# ground-station.net
KiCad netlist of a schematic drawn in Altium Designer
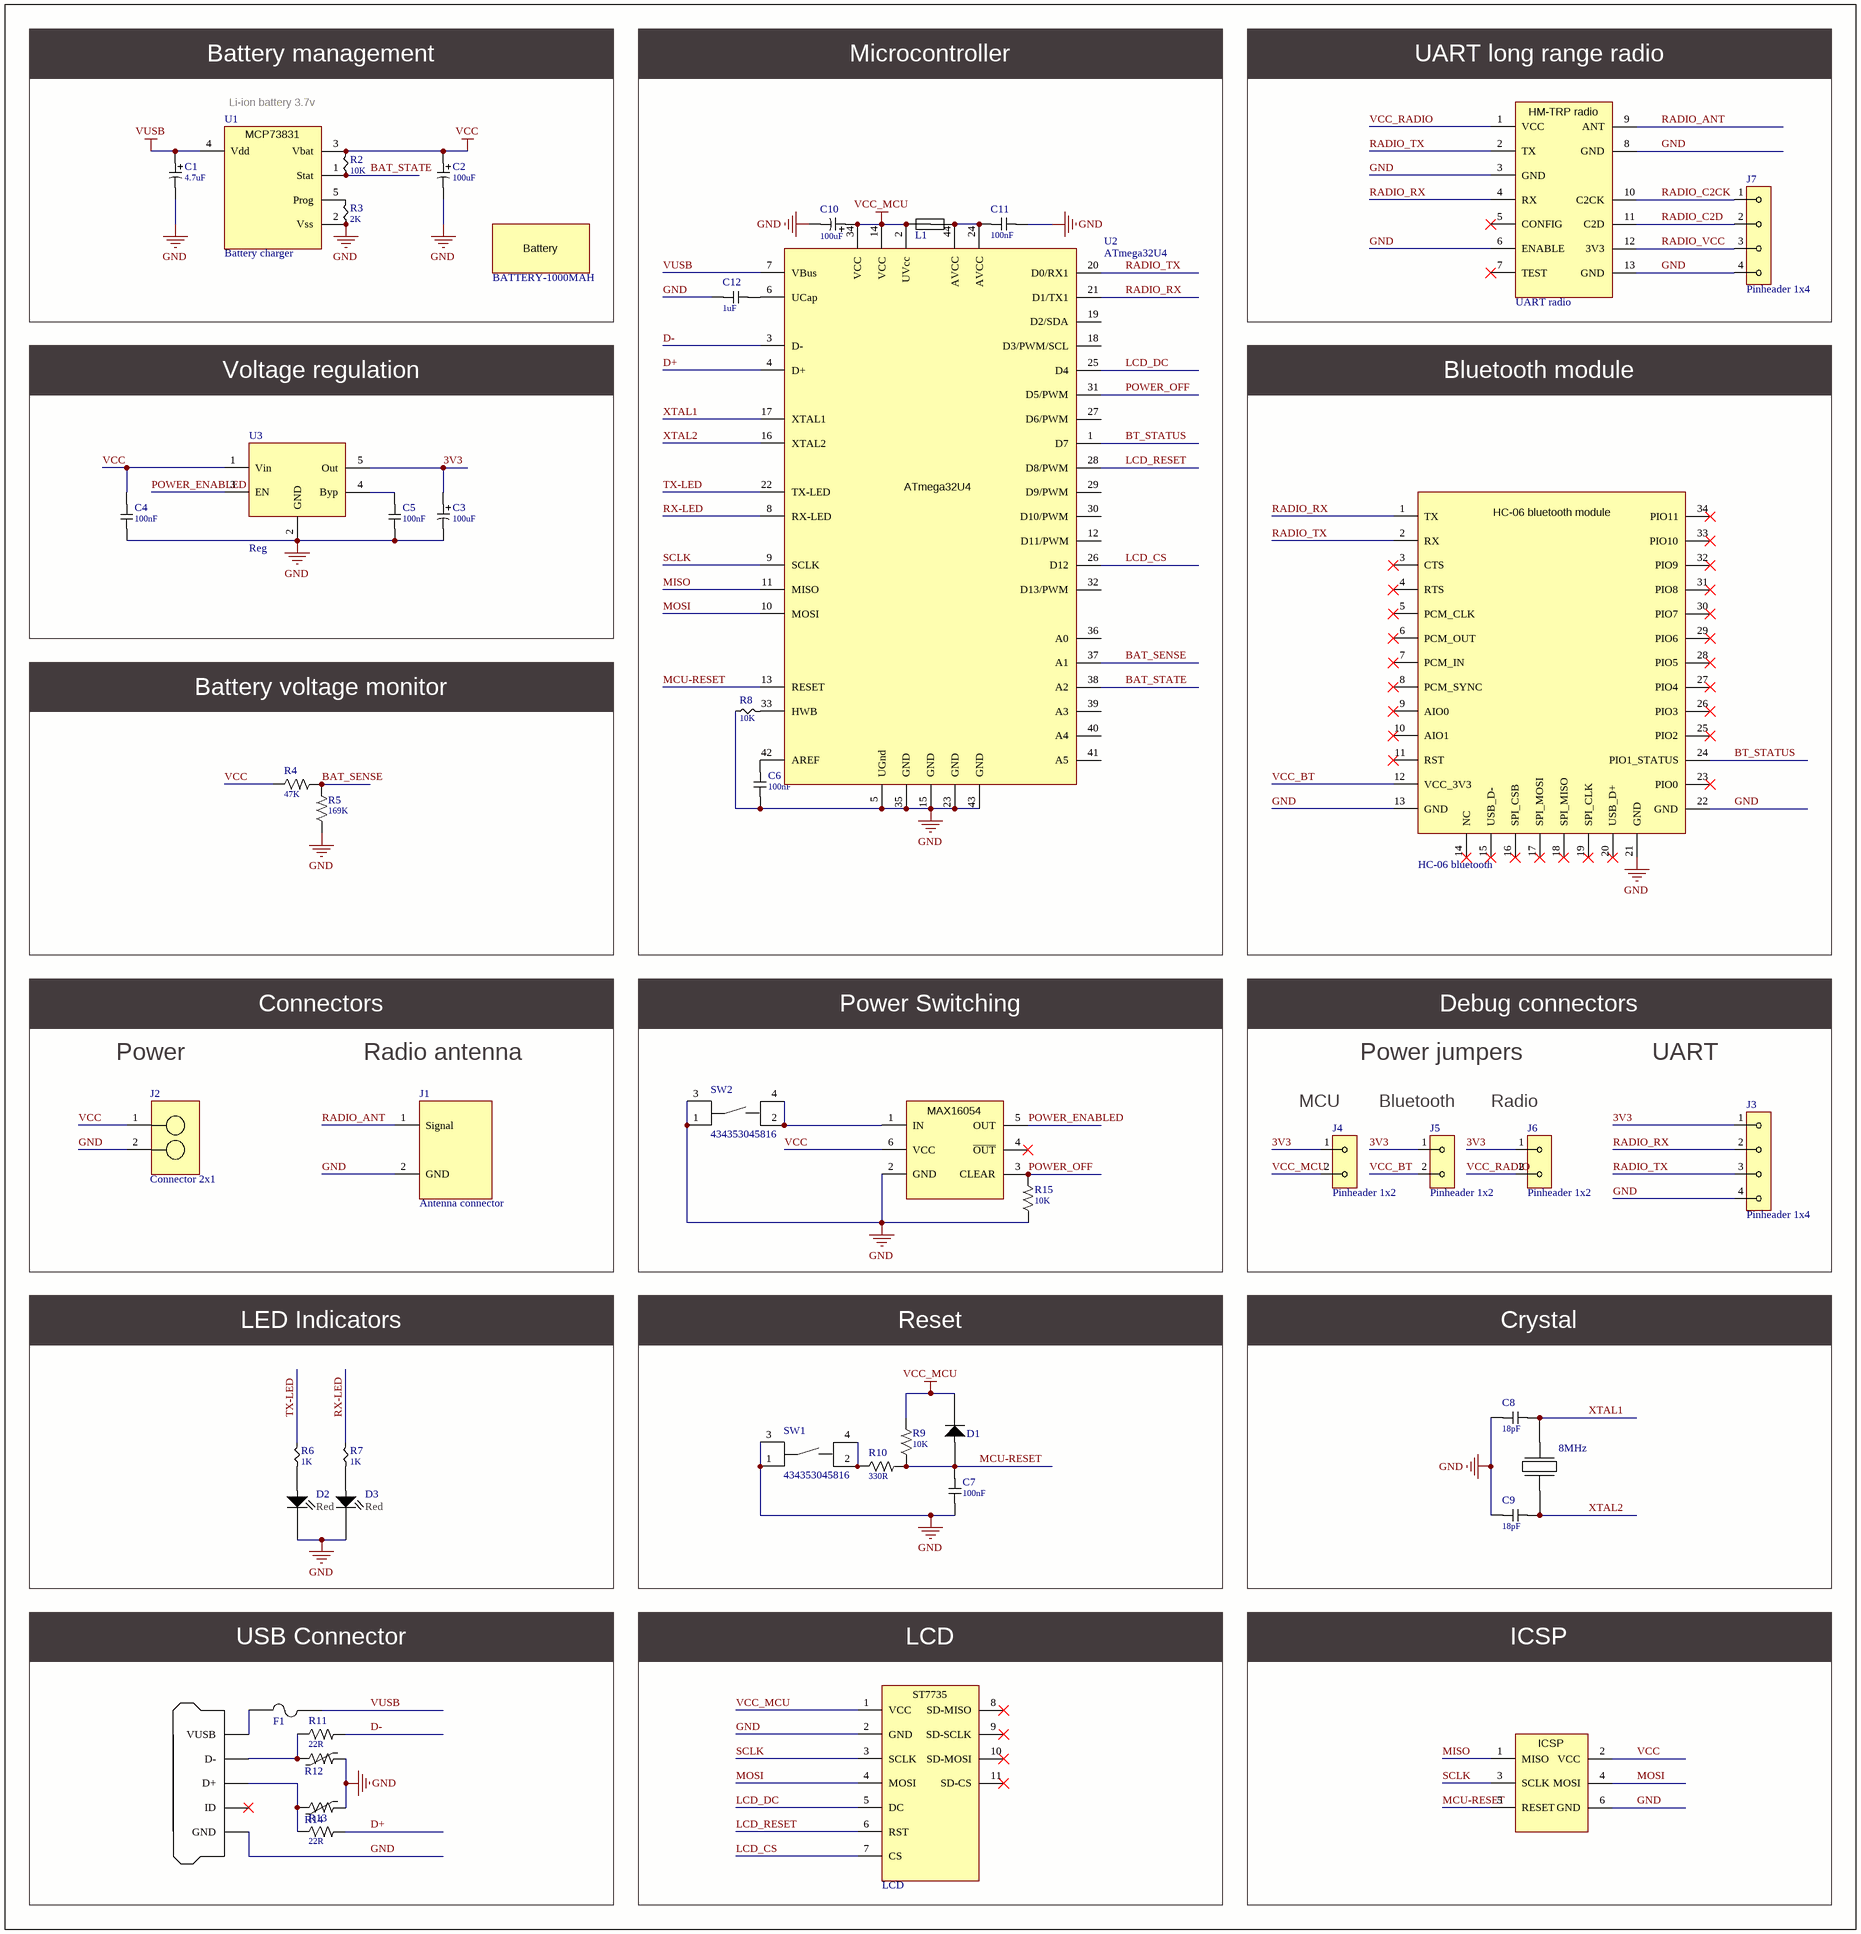
[diagram p0: ground-station.SchDoc]

(export (version "E")
  (design (tool "Eeschema 10.0.6"))
  (components
    (comp (ref "B1")
      (value "BATTERY-1000MAH")
      (footprint "BATTERY-1000MAH")
      (description "Battery")
      (libsource (lib "custom") (part "BATTERY-1000MAH"))
    )
    (comp (ref "BT1")
      (value "HC-06 bluetooth")
      (footprint "HC-06-BLUETOOTH")
      (description "HC-06 bluetooth module")
      (libsource (lib "custom") (part "HC-06-BLUETOOTH"))
    )
    (comp (ref "C1")
      (value "4.7uF")
      (footprint "CAP-0603-POL")
      (description "Polarized capacitor")
      (fields (field (name "Comment") "CAPACITOR-POLARIZED"))
      (libsource (lib "custom") (part "CAPACITOR-POLARIZED"))
    )
    (comp (ref "C2")
      (value "100uF")
      (footprint "CAP-1206-POL")
      (description "Polarized capacitor")
      (fields (field (name "Comment") "CAPACITOR-POLARIZED"))
      (libsource (lib "custom") (part "CAPACITOR-POLARIZED"))
    )
    (comp (ref "C3")
      (value "100uF")
      (footprint "CAP-1206-POL")
      (description "Polarized capacitor")
      (fields (field (name "Comment") "CAPACITOR-POLARIZED"))
      (libsource (lib "custom") (part "CAPACITOR-POLARIZED"))
    )
    (comp (ref "C4")
      (value "100nF")
      (footprint "CAP-0603-GEN")
      (description "Capacitor")
      (fields (field (name "Comment") "CAPACITOR"))
      (libsource (lib "custom") (part "CAPACITOR"))
    )
    (comp (ref "C5")
      (value "100nF")
      (footprint "CAP-0603-GEN")
      (description "Capacitor")
      (fields (field (name "Comment") "CAPACITOR"))
      (libsource (lib "custom") (part "CAPACITOR"))
    )
    (comp (ref "C6")
      (value "100nF")
      (footprint "CAP-0603-GEN")
      (description "Capacitor")
      (fields (field (name "Comment") "CAPACITOR"))
      (libsource (lib "schematic-library") (part "CAPACITOR"))
    )
    (comp (ref "C7")
      (value "100nF")
      (footprint "CAP-0603-GEN")
      (description "Capacitor")
      (fields (field (name "Comment") "CAPACITOR"))
      (libsource (lib "schematic-library") (part "CAPACITOR"))
    )
    (comp (ref "C8")
      (value "18pF")
      (footprint "CAP-0603-GEN")
      (description "Capacitor")
      (fields (field (name "Comment") "CAPACITOR"))
      (libsource (lib "schematic-library") (part "CAPACITOR"))
    )
    (comp (ref "C9")
      (value "18pF")
      (footprint "CAP-0603-GEN")
      (description "Capacitor")
      (fields (field (name "Comment") "CAPACITOR"))
      (libsource (lib "schematic-library") (part "CAPACITOR"))
    )
    (comp (ref "C10")
      (value "100uF")
      (footprint "CAP-1206-POL")
      (description "Polarized capacitor")
      (fields (field (name "Comment") "CAPACITOR-POLARIZED"))
      (libsource (lib "schematic-library") (part "CAPACITOR-POLARIZED"))
    )
    (comp (ref "C11")
      (value "100nF")
      (footprint "CAP-0603-GEN")
      (description "Capacitor")
      (fields (field (name "Comment") "CAPACITOR"))
      (libsource (lib "schematic-library") (part "CAPACITOR"))
    )
    (comp (ref "C12")
      (value "1uF")
      (footprint "CAP-0603-GEN")
      (description "Capacitor")
      (fields (field (name "Comment") "CAPACITOR"))
      (libsource (lib "schematic-library") (part "CAPACITOR"))
    )
    (comp (ref "D1")
      (value "DIODE")
      (footprint "DIODE-0603")
      (description "Diode")
      (libsource (lib "schematic-library") (part "DIODE"))
    )
    (comp (ref "D2")
      (value "LED")
      (footprint "LED-0603")
      (fields (field (name "COLOR") "Red"))
      (libsource (lib "schematic-library") (part "LED"))
    )
    (comp (ref "D3")
      (value "LED")
      (footprint "LED-0603")
      (fields (field (name "COLOR") "Red"))
      (libsource (lib "schematic-library") (part "LED"))
    )
    (comp (ref "F1")
      (value "Fuse")
      (footprint "FUSE-0603")
      (libsource (lib "schematic-library") (part "FUSE"))
    )
    (comp (ref "ICSP")
      (value "ICSP")
      (footprint "ICSP-HEADER")
      (description "In-circuit serial programmer interface")
      (libsource (lib "schematic-library") (part "ICSP"))
    )
    (comp (ref "J1")
      (value "Antenna connector")
      (footprint "SMA-PCB")
      (libsource (lib "custom") (part "ANTENNA-CONNECTOR"))
    )
    (comp (ref "J2")
      (value "Connector 2x1")
      (footprint "JST-PH-1x2")
      (description "Single row two contact connector")
      (libsource (lib "custom") (part "CONNECTOR-1x2"))
    )
    (comp (ref "J3")
      (value "Pinheader 1x4")
      (footprint "PINHEADER-1x4-right-angle")
      (description "Single row four pin header")
      (libsource (lib "custom") (part "PINHEADER-1x4"))
    )
    (comp (ref "J4")
      (value "Pinheader 1x2")
      (footprint "PINHEADER-1x2-SMALL-JUMPER")
      (description "Single row two pin header")
      (libsource (lib "custom") (part "PINHEADER-1x2"))
    )
    (comp (ref "J5")
      (value "Pinheader 1x2")
      (footprint "PINHEADER-1x2-SMALL-JUMPER")
      (description "Single row two pin header")
      (libsource (lib "custom") (part "PINHEADER-1x2"))
    )
    (comp (ref "J6")
      (value "Pinheader 1x2")
      (footprint "PINHEADER-1x2-SMALL-JUMPER")
      (description "Single row two pin header")
      (libsource (lib "custom") (part "PINHEADER-1x2"))
    )
    (comp (ref "J7")
      (value "Pinheader 1x4")
      (footprint "PINHEADER-1x4")
      (description "Single row four pin header")
      (libsource (lib "schematic-library") (part "PINHEADER-1x4"))
    )
    (comp (ref "L1")
      (value "Ferrite bead")
      (footprint "FERRITE-0603")
      (libsource (lib "schematic-library") (part "FERRITE-BEAD"))
    )
    (comp (ref "LCD1")
      (value "LCD")
      (footprint "ST7735")
      (description "ST7735 color LCD")
      (libsource (lib "custom") (part "ST7735"))
    )
    (comp (ref "R1")
      (value "UART radio")
      (footprint "HM-TRP")
      (description "UART long range radio")
      (libsource (lib "schematic-library") (part "HM-TRP"))
    )
    (comp (ref "R2")
      (value "10K")
      (footprint "RESISTOR-0603")
      (description "Resistor")
      (libsource (lib "custom") (part "RESISTOR-SMALL"))
    )
    (comp (ref "R3")
      (value "2K")
      (footprint "RESISTOR-0603")
      (description "Resistor")
      (libsource (lib "custom") (part "RESISTOR-SMALL"))
    )
    (comp (ref "R4")
      (value "47K")
      (footprint "RESISTOR-0603")
      (description "Resistor")
      (fields (field (name "Comment") "RESISTOR"))
      (libsource (lib "custom") (part "RESISTOR"))
    )
    (comp (ref "R5")
      (value "169K")
      (footprint "RESISTOR-0603")
      (description "Resistor")
      (fields (field (name "Comment") "RESISTOR"))
      (libsource (lib "custom") (part "RESISTOR"))
    )
    (comp (ref "R6")
      (value "1K")
      (footprint "RESISTOR-0603")
      (description "Resistor")
      (libsource (lib "schematic-library") (part "RESISTOR-SMALL"))
    )
    (comp (ref "R7")
      (value "1K")
      (footprint "RESISTOR-0603")
      (description "Resistor")
      (libsource (lib "schematic-library") (part "RESISTOR-SMALL"))
    )
    (comp (ref "R8")
      (value "10K")
      (footprint "RESISTOR-0603")
      (description "Resistor")
      (libsource (lib "schematic-library") (part "RESISTOR-SMALL"))
    )
    (comp (ref "R9")
      (value "10K")
      (footprint "RESISTOR-0603")
      (description "Resistor")
      (fields (field (name "Comment") "RESISTOR"))
      (libsource (lib "schematic-library") (part "RESISTOR"))
    )
    (comp (ref "R10")
      (value "330R")
      (footprint "RESISTOR-0603")
      (description "Resistor")
      (fields (field (name "Comment") "RESISTOR"))
      (libsource (lib "schematic-library") (part "RESISTOR"))
    )
    (comp (ref "R11")
      (value "22R")
      (footprint "RESISTOR-0603")
      (description "Resistor")
      (fields (field (name "Comment") "RESISTOR"))
      (libsource (lib "schematic-library") (part "RESISTOR"))
    )
    (comp (ref "R12")
      (value "Varistor")
      (footprint "RESISTOR-0603")
      (libsource (lib "schematic-library") (part "VARISTOR"))
    )
    (comp (ref "R13")
      (value "22R")
      (footprint "RESISTOR-0603")
      (description "Resistor")
      (fields (field (name "Comment") "RESISTOR"))
      (libsource (lib "schematic-library") (part "RESISTOR"))
    )
    (comp (ref "R14")
      (value "Varistor")
      (footprint "RESISTOR-0603")
      (libsource (lib "schematic-library") (part "VARISTOR"))
    )
    (comp (ref "R15")
      (value "10K")
      (footprint "RESISTOR-0603")
      (description "Resistor")
      (fields (field (name "Comment") "RESISTOR"))
      (libsource (lib "schematic-library") (part "RESISTOR"))
    )
    (comp (ref "SW1")
      (value "434353045816")
      (footprint "WURTH-TACTILE-434353045816")
      (description "WS-TASU SMD Tact Switch 4.7X3.5 mm side push")
      (fields
        (field (name "MANUFACTURER") "W毓rth Elektronik eiSos GmbH & Co.KG")
        (field (name "PARTNO") "434351045816")
        (field (name "CREAT BY") "Karrer Zheng")
      )
      (libsource (lib "schematic-library") (part "WURTH-TACTILE-434353045816"))
    )
    (comp (ref "SW2")
      (value "434353045816")
      (footprint "WURTH-TACTILE-434353045816")
      (description "WS-TASU SMD Tact Switch 4.7X3.5 mm side push")
      (fields
        (field (name "MANUFACTURER") "W毓rth Elektronik eiSos GmbH & Co.KG")
        (field (name "PARTNO") "434351045816")
        (field (name "CREAT BY") "Karrer Zheng")
      )
      (libsource (lib "schematic-library") (part "WURTH-TACTILE-434353045816"))
    )
    (comp (ref "U1")
      (value "Battery charger")
      (footprint "SOT23-5")
      (description "Single cell battery management")
      (libsource (lib "custom") (part "BATTERY-CHARGER-MCP73831"))
    )
    (comp (ref "U2")
      (value "ATmega32U4")
      (footprint "TQFP44")
      (libsource (lib "schematic-library") (part "ATmega32U4"))
    )
    (comp (ref "U3")
      (value "Reg")
      (footprint "SOT23-5")
      (description "Voltage regulator")
      (libsource (lib "custom") (part "SOT23-REG"))
    )
    (comp (ref "U4")
      (value "on/off controller")
      (footprint "SOT23-6")
      (description "Pushbutton on/off controller")
      (libsource (lib "schematic-library") (part "MAX16054"))
    )
    (comp (ref "USB1")
      (value "USB Connector")
      (footprint "USB-MICRO-B")
      (libsource (lib "schematic-library") (part "USB-CONNECTOR"))
    )
    (comp (ref "Y1")
      (value "CRYSTAL")
      (footprint "CRYSTAL-5032")
      (description "Crystal oscillator")
      (fields (field (name "FREQUENCY") "8MHz"))
      (libsource (lib "schematic-library") (part "CRYSTAL"))
    )
  )
  (nets
    (net (code "1") (name "/3V3") (class "Default")
      (node (ref "C3") (pin "1") (pinfunction "1_1") (pintype "passive"))
      (node (ref "J3") (pin "1") (pinfunction "1_1") (pintype "passive"))
      (node (ref "J4") (pin "1") (pinfunction "1_1") (pintype "passive"))
      (node (ref "J5") (pin "1") (pinfunction "1_1") (pintype "passive"))
      (node (ref "J6") (pin "1") (pinfunction "1_1") (pintype "passive"))
      (node (ref "U3") (pin "5") (pinfunction "Out_5") (pintype "passive"))
    )
    (net (code "2") (name "/BAT_SENSE") (class "Default")
      (node (ref "R4") (pin "2") (pinfunction "2_2") (pintype "passive"))
      (node (ref "R5") (pin "2") (pinfunction "2_2") (pintype "passive"))
      (node (ref "U2") (pin "37") (pinfunction "A1_37") (pintype "power_in"))
    )
    (net (code "3") (name "/BAT_STATE") (class "Default")
      (node (ref "R2") (pin "1") (pinfunction "1_1") (pintype "passive"))
      (node (ref "U1") (pin "1") (pinfunction "Stat_1") (pintype "passive"))
      (node (ref "U2") (pin "38") (pinfunction "A2_38") (pintype "power_in"))
    )
    (net (code "4") (name "/BT_STATUS") (class "Default")
      (node (ref "BT1") (pin "24") (pinfunction "PIO1_STATUS_24") (pintype "passive"))
      (node (ref "U2") (pin "1") (pinfunction "D7_1") (pintype "power_in"))
    )
    (net (code "5") (name "/D+") (class "Default")
      (node (ref "R13") (pin "2") (pinfunction "2_2") (pintype "passive"))
      (node (ref "U2") (pin "4") (pinfunction "D+_4") (pintype "power_in"))
    )
    (net (code "6") (name "/D-") (class "Default")
      (node (ref "R11") (pin "2") (pinfunction "2_2") (pintype "passive"))
      (node (ref "U2") (pin "3") (pinfunction "D-_3") (pintype "power_in"))
    )
    (net (code "7") (name "/LCD_CS") (class "Default")
      (node (ref "LCD1") (pin "7") (pinfunction "CS_7") (pintype "passive"))
      (node (ref "U2") (pin "26") (pinfunction "D12_26") (pintype "power_in"))
    )
    (net (code "8") (name "/LCD_DC") (class "Default")
      (node (ref "LCD1") (pin "5") (pinfunction "DC_5") (pintype "passive"))
      (node (ref "U2") (pin "25") (pinfunction "D4_25") (pintype "power_in"))
    )
    (net (code "9") (name "/LCD_RESET") (class "Default")
      (node (ref "LCD1") (pin "6") (pinfunction "RST_6") (pintype "passive"))
      (node (ref "U2") (pin "28") (pinfunction "D8/PWM_28") (pintype "power_in"))
    )
    (net (code "10") (name "/MCU-RESET") (class "Default")
      (node (ref "C7") (pin "2") (pinfunction "2_2") (pintype "passive"))
      (node (ref "D1") (pin "1") (pinfunction "Anode_1") (pintype "passive"))
      (node (ref "ICSP") (pin "5") (pinfunction "RESET_5") (pintype "passive"))
      (node (ref "R10") (pin "2") (pinfunction "2_2") (pintype "passive"))
      (node (ref "R9") (pin "1") (pinfunction "1_1") (pintype "passive"))
      (node (ref "U2") (pin "13") (pinfunction "RESET_13") (pintype "power_in"))
    )
    (net (code "11") (name "/MISO") (class "Default")
      (node (ref "ICSP") (pin "1") (pinfunction "MISO_1") (pintype "passive"))
      (node (ref "U2") (pin "11") (pinfunction "MISO_11") (pintype "power_in"))
    )
    (net (code "12") (name "/MOSI") (class "Default")
      (node (ref "ICSP") (pin "4") (pinfunction "MOSI_4") (pintype "passive"))
      (node (ref "LCD1") (pin "4") (pinfunction "MOSI_4") (pintype "passive"))
      (node (ref "U2") (pin "10") (pinfunction "MOSI_10") (pintype "power_in"))
    )
    (net (code "13") (name "/POWER_ENABLED") (class "Default")
      (node (ref "U3") (pin "3") (pinfunction "EN_3") (pintype "passive"))
      (node (ref "U4") (pin "5") (pinfunction "OUT_5") (pintype "passive"))
    )
    (net (code "14") (name "/POWER_OFF") (class "Default")
      (node (ref "R15") (pin "2") (pinfunction "2_2") (pintype "passive"))
      (node (ref "U2") (pin "31") (pinfunction "D5/PWM_31") (pintype "power_in"))
      (node (ref "U4") (pin "3") (pinfunction "CLEAR_3") (pintype "passive"))
    )
    (net (code "15") (name "/RADIO_ANT") (class "Default")
      (node (ref "J1") (pin "1") (pinfunction "Signal_1") (pintype "passive"))
      (node (ref "R1") (pin "9") (pinfunction "ANT_9") (pintype "passive"))
    )
    (net (code "16") (name "/RADIO_C2CK") (class "Default")
      (node (ref "J7") (pin "1") (pinfunction "1_1") (pintype "passive"))
      (node (ref "R1") (pin "10") (pinfunction "C2CK_10") (pintype "passive"))
    )
    (net (code "17") (name "/RADIO_C2D") (class "Default")
      (node (ref "J7") (pin "2") (pinfunction "2_2") (pintype "passive"))
      (node (ref "R1") (pin "11") (pinfunction "C2D_11") (pintype "passive"))
    )
    (net (code "18") (name "/RADIO_RX") (class "Default")
      (node (ref "BT1") (pin "1") (pinfunction "TX_1") (pintype "passive"))
      (node (ref "J3") (pin "2") (pinfunction "2_2") (pintype "passive"))
      (node (ref "R1") (pin "4") (pinfunction "RX_4") (pintype "passive"))
      (node (ref "U2") (pin "21") (pinfunction "D1/TX1_21") (pintype "power_in"))
    )
    (net (code "19") (name "/RADIO_TX") (class "Default")
      (node (ref "BT1") (pin "2") (pinfunction "RX_2") (pintype "passive"))
      (node (ref "J3") (pin "3") (pinfunction "3_3") (pintype "passive"))
      (node (ref "R1") (pin "2") (pinfunction "TX_2") (pintype "passive"))
      (node (ref "U2") (pin "20") (pinfunction "D0/RX1_20") (pintype "power_in"))
    )
    (net (code "20") (name "/RADIO_VCC") (class "Default")
      (node (ref "J7") (pin "3") (pinfunction "3_3") (pintype "passive"))
      (node (ref "R1") (pin "12") (pinfunction "3V3_12") (pintype "passive"))
    )
    (net (code "21") (name "/RX-LED") (class "Default")
      (node (ref "R7") (pin "2") (pinfunction "2_2") (pintype "passive"))
      (node (ref "U2") (pin "8") (pinfunction "RX-LED_8") (pintype "power_in"))
    )
    (net (code "22") (name "/SCLK") (class "Default")
      (node (ref "ICSP") (pin "3") (pinfunction "SCLK_3") (pintype "passive"))
      (node (ref "LCD1") (pin "3") (pinfunction "SCLK_3") (pintype "passive"))
      (node (ref "U2") (pin "9") (pinfunction "SCLK_9") (pintype "power_in"))
    )
    (net (code "23") (name "/TX-LED") (class "Default")
      (node (ref "R6") (pin "2") (pinfunction "2_2") (pintype "passive"))
      (node (ref "U2") (pin "22") (pinfunction "TX-LED_22") (pintype "power_in"))
    )
    (net (code "24") (name "/VCC_BT") (class "Default")
      (node (ref "BT1") (pin "12") (pinfunction "VCC_3V3_12") (pintype "passive"))
      (node (ref "J5") (pin "2") (pinfunction "2_2") (pintype "passive"))
    )
    (net (code "25") (name "/VCC_RADIO") (class "Default")
      (node (ref "J6") (pin "2") (pinfunction "2_2") (pintype "passive"))
      (node (ref "R1") (pin "1") (pinfunction "VCC_1") (pintype "passive"))
    )
    (net (code "26") (name "/XTAL1") (class "Default")
      (node (ref "C8") (pin "2") (pinfunction "2_2") (pintype "passive"))
      (node (ref "U2") (pin "17") (pinfunction "XTAL1_17") (pintype "power_in"))
      (node (ref "Y1") (pin "2") (pinfunction "2_2") (pintype "passive"))
    )
    (net (code "27") (name "/XTAL2") (class "Default")
      (node (ref "C9") (pin "2") (pinfunction "2_2") (pintype "passive"))
      (node (ref "U2") (pin "16") (pinfunction "XTAL2_16") (pintype "power_in"))
      (node (ref "Y1") (pin "1") (pinfunction "1_1") (pintype "passive"))
    )
    (net (code "28") (name "GND") (class "Default")
      (node (ref "BT1") (pin "13") (pinfunction "GND_13") (pintype "passive"))
      (node (ref "BT1") (pin "21") (pinfunction "GND_21") (pintype "passive"))
      (node (ref "BT1") (pin "22") (pinfunction "GND_22") (pintype "passive"))
      (node (ref "C1") (pin "2") (pinfunction "2_2") (pintype "passive"))
      (node (ref "C10") (pin "2") (pinfunction "2_2") (pintype "passive"))
      (node (ref "C11") (pin "2") (pinfunction "2_2") (pintype "passive"))
      (node (ref "C12") (pin "1") (pinfunction "1_1") (pintype "passive"))
      (node (ref "C2") (pin "2") (pinfunction "2_2") (pintype "passive"))
      (node (ref "C3") (pin "2") (pinfunction "2_2") (pintype "passive"))
      (node (ref "C4") (pin "1") (pinfunction "1_1") (pintype "passive"))
      (node (ref "C5") (pin "1") (pinfunction "1_1") (pintype "passive"))
      (node (ref "C6") (pin "1") (pinfunction "1_1") (pintype "passive"))
      (node (ref "C7") (pin "1") (pinfunction "1_1") (pintype "passive"))
      (node (ref "C8") (pin "1") (pinfunction "1_1") (pintype "passive"))
      (node (ref "C9") (pin "1") (pinfunction "1_1") (pintype "passive"))
      (node (ref "D2") (pin "2") (pinfunction "Cathode_2") (pintype "passive"))
      (node (ref "D3") (pin "2") (pinfunction "Cathode_2") (pintype "passive"))
      (node (ref "ICSP") (pin "6") (pinfunction "GND_6") (pintype "passive"))
      (node (ref "J1") (pin "2") (pinfunction "GND_2") (pintype "passive"))
      (node (ref "J2") (pin "2") (pinfunction "2_2") (pintype "passive"))
      (node (ref "J3") (pin "4") (pinfunction "4_4") (pintype "passive"))
      (node (ref "J7") (pin "4") (pinfunction "4_4") (pintype "passive"))
      (node (ref "LCD1") (pin "2") (pinfunction "GND_2") (pintype "passive"))
      (node (ref "R1") (pin "13") (pinfunction "GND_13") (pintype "passive"))
      (node (ref "R1") (pin "3") (pinfunction "GND_3") (pintype "passive"))
      (node (ref "R1") (pin "6") (pinfunction "ENABLE_6") (pintype "passive"))
      (node (ref "R1") (pin "8") (pinfunction "GND_8") (pintype "passive"))
      (node (ref "R12") (pin "2") (pinfunction "2_2") (pintype "passive"))
      (node (ref "R14") (pin "2") (pinfunction "2_2") (pintype "passive"))
      (node (ref "R15") (pin "1") (pinfunction "1_1") (pintype "passive"))
      (node (ref "R3") (pin "1") (pinfunction "1_1") (pintype "passive"))
      (node (ref "R5") (pin "1") (pinfunction "1_1") (pintype "passive"))
      (node (ref "R8") (pin "1") (pinfunction "1_1") (pintype "passive"))
      (node (ref "SW1") (pin "1") (pinfunction "1_1") (pintype "passive"))
      (node (ref "SW1") (pin "3") (pinfunction "3_3") (pintype "passive"))
      (node (ref "SW2") (pin "1") (pinfunction "1_1") (pintype "passive"))
      (node (ref "SW2") (pin "3") (pinfunction "3_3") (pintype "passive"))
      (node (ref "U1") (pin "2") (pinfunction "Vss_2") (pintype "passive"))
      (node (ref "U2") (pin "15") (pinfunction "GND_15") (pintype "power_in"))
      (node (ref "U2") (pin "23") (pinfunction "GND_23") (pintype "power_in"))
      (node (ref "U2") (pin "35") (pinfunction "GND_35") (pintype "power_in"))
      (node (ref "U2") (pin "43") (pinfunction "GND_43") (pintype "power_in"))
      (node (ref "U2") (pin "5") (pinfunction "UGnd_5") (pintype "power_in"))
      (node (ref "U3") (pin "2") (pinfunction "GND_2") (pintype "passive"))
      (node (ref "U4") (pin "2") (pinfunction "GND_2") (pintype "passive"))
      (node (ref "USB1") (pin "5") (pinfunction "GND_5") (pintype "passive"))
    )
    (net (code "29") (name "Net-(C11-Pad1)") (class "Default")
      (node (ref "C11") (pin "1") (pinfunction "1_1") (pintype "passive"))
      (node (ref "L1") (pin "1") (pinfunction "1_1") (pintype "passive"))
      (node (ref "U2") (pin "24") (pinfunction "AVCC_24") (pintype "power_in"))
      (node (ref "U2") (pin "44") (pinfunction "AVCC_44") (pintype "power_in"))
    )
    (net (code "30") (name "Net-(D2-Anode)") (class "Default")
      (node (ref "D2") (pin "1") (pinfunction "Anode_1") (pintype "passive"))
      (node (ref "R6") (pin "1") (pinfunction "1_1") (pintype "passive"))
    )
    (net (code "31") (name "Net-(D3-Anode)") (class "Default")
      (node (ref "D3") (pin "1") (pinfunction "Anode_1") (pintype "passive"))
      (node (ref "R7") (pin "1") (pinfunction "1_1") (pintype "passive"))
    )
    (net (code "32") (name "Net-(R10-Pad1)") (class "Default")
      (node (ref "R10") (pin "1") (pinfunction "1_1") (pintype "passive"))
      (node (ref "SW1") (pin "2") (pinfunction "2_2") (pintype "passive"))
      (node (ref "SW1") (pin "4") (pinfunction "4_4") (pintype "passive"))
    )
    (net (code "33") (name "Net-(U1-Prog)") (class "Default")
      (node (ref "R3") (pin "2") (pinfunction "2_2") (pintype "passive"))
      (node (ref "U1") (pin "5") (pinfunction "Prog_5") (pintype "passive"))
    )
    (net (code "34") (name "Net-(U2-AREF)") (class "Default")
      (node (ref "C6") (pin "2") (pinfunction "2_2") (pintype "passive"))
      (node (ref "U2") (pin "42") (pinfunction "AREF_42") (pintype "power_in"))
    )
    (net (code "35") (name "Net-(U2-HWB)") (class "Default")
      (node (ref "R8") (pin "2") (pinfunction "2_2") (pintype "passive"))
      (node (ref "U2") (pin "33") (pinfunction "HWB_33") (pintype "power_in"))
    )
    (net (code "36") (name "Net-(U2-UCap)") (class "Default")
      (node (ref "C12") (pin "2") (pinfunction "2_2") (pintype "passive"))
      (node (ref "U2") (pin "6") (pinfunction "UCap_6") (pintype "power_in"))
    )
    (net (code "37") (name "Net-(U3-Byp)") (class "Default")
      (node (ref "C5") (pin "2") (pinfunction "2_2") (pintype "passive"))
      (node (ref "U3") (pin "4") (pinfunction "Byp_4") (pintype "passive"))
    )
    (net (code "38") (name "Net-(U4-IN)") (class "Default")
      (node (ref "SW2") (pin "2") (pinfunction "2_2") (pintype "passive"))
      (node (ref "SW2") (pin "4") (pinfunction "4_4") (pintype "passive"))
      (node (ref "U4") (pin "1") (pinfunction "IN_1") (pintype "passive"))
    )
    (net (code "39") (name "Net-(USB1-D+)") (class "Default")
      (node (ref "R13") (pin "1") (pinfunction "1_1") (pintype "passive"))
      (node (ref "R14") (pin "1") (pinfunction "1_1") (pintype "passive"))
      (node (ref "USB1") (pin "3") (pinfunction "D+_3") (pintype "passive"))
    )
    (net (code "40") (name "Net-(USB1-D-)") (class "Default")
      (node (ref "R11") (pin "1") (pinfunction "1_1") (pintype "passive"))
      (node (ref "R12") (pin "1") (pinfunction "1_1") (pintype "passive"))
      (node (ref "USB1") (pin "2") (pinfunction "D-_2") (pintype "passive"))
    )
    (net (code "41") (name "Net-(USB1-VUSB)") (class "Default")
      (node (ref "F1") (pin "1") (pinfunction "1_1") (pintype "passive"))
      (node (ref "USB1") (pin "1") (pinfunction "VUSB_1") (pintype "passive"))
    )
    (net (code "42") (name "VCC") (class "Default")
      (node (ref "C2") (pin "1") (pinfunction "1_1") (pintype "passive"))
      (node (ref "C4") (pin "2") (pinfunction "2_2") (pintype "passive"))
      (node (ref "ICSP") (pin "2") (pinfunction "VCC_2") (pintype "passive"))
      (node (ref "J2") (pin "1") (pinfunction "1_1") (pintype "passive"))
      (node (ref "R2") (pin "2") (pinfunction "2_2") (pintype "passive"))
      (node (ref "R4") (pin "1") (pinfunction "1_1") (pintype "passive"))
      (node (ref "U1") (pin "3") (pinfunction "Vbat_3") (pintype "passive"))
      (node (ref "U3") (pin "1") (pinfunction "Vin_1") (pintype "passive"))
      (node (ref "U4") (pin "6") (pinfunction "VCC_6") (pintype "passive"))
    )
    (net (code "43") (name "VCC_MCU") (class "Default")
      (node (ref "C10") (pin "1") (pinfunction "1_1") (pintype "passive"))
      (node (ref "D1") (pin "2") (pinfunction "Cathode_2") (pintype "passive"))
      (node (ref "J4") (pin "2") (pinfunction "2_2") (pintype "passive"))
      (node (ref "L1") (pin "2") (pinfunction "2_2") (pintype "passive"))
      (node (ref "LCD1") (pin "1") (pinfunction "VCC_1") (pintype "passive"))
      (node (ref "R9") (pin "2") (pinfunction "2_2") (pintype "passive"))
      (node (ref "U2") (pin "14") (pinfunction "VCC_14") (pintype "power_in"))
      (node (ref "U2") (pin "2") (pinfunction "UVcc_2") (pintype "power_in"))
      (node (ref "U2") (pin "34") (pinfunction "VCC_34") (pintype "power_in"))
    )
    (net (code "44") (name "VUSB") (class "Default")
      (node (ref "C1") (pin "1") (pinfunction "1_1") (pintype "passive"))
      (node (ref "F1") (pin "2") (pinfunction "2_2") (pintype "passive"))
      (node (ref "U1") (pin "4") (pinfunction "Vdd_4") (pintype "passive"))
      (node (ref "U2") (pin "7") (pinfunction "VBus_7") (pintype "power_in"))
    )
    (net (code "45") (name "unconnected-(BT1-AIO0-Pad9)") (class "Default")
      (node (ref "BT1") (pin "9") (pinfunction "AIO0_9") (pintype "passive+no_connect"))
    )
    (net (code "46") (name "unconnected-(BT1-AIO1-Pad10)") (class "Default")
      (node (ref "BT1") (pin "10") (pinfunction "AIO1_10") (pintype "passive+no_connect"))
    )
    (net (code "47") (name "unconnected-(BT1-CTS-Pad3)") (class "Default")
      (node (ref "BT1") (pin "3") (pinfunction "CTS_3") (pintype "passive+no_connect"))
    )
    (net (code "48") (name "unconnected-(BT1-NC-Pad14)") (class "Default")
      (node (ref "BT1") (pin "14") (pinfunction "NC_14") (pintype "passive+no_connect"))
    )
    (net (code "49") (name "unconnected-(BT1-PCM_CLK-Pad5)") (class "Default")
      (node (ref "BT1") (pin "5") (pinfunction "PCM_CLK_5") (pintype "passive+no_connect"))
    )
    (net (code "50") (name "unconnected-(BT1-PCM_IN-Pad7)") (class "Default")
      (node (ref "BT1") (pin "7") (pinfunction "PCM_IN_7") (pintype "passive+no_connect"))
    )
    (net (code "51") (name "unconnected-(BT1-PCM_OUT-Pad6)") (class "Default")
      (node (ref "BT1") (pin "6") (pinfunction "PCM_OUT_6") (pintype "passive+no_connect"))
    )
    (net (code "52") (name "unconnected-(BT1-PCM_SYNC-Pad8)") (class "Default")
      (node (ref "BT1") (pin "8") (pinfunction "PCM_SYNC_8") (pintype "passive+no_connect"))
    )
    (net (code "53") (name "unconnected-(BT1-PIO0-Pad23)") (class "Default")
      (node (ref "BT1") (pin "23") (pinfunction "PIO0_23") (pintype "passive+no_connect"))
    )
    (net (code "54") (name "unconnected-(BT1-PIO2-Pad25)") (class "Default")
      (node (ref "BT1") (pin "25") (pinfunction "PIO2_25") (pintype "passive+no_connect"))
    )
    (net (code "55") (name "unconnected-(BT1-PIO3-Pad26)") (class "Default")
      (node (ref "BT1") (pin "26") (pinfunction "PIO3_26") (pintype "passive+no_connect"))
    )
    (net (code "56") (name "unconnected-(BT1-PIO4-Pad27)") (class "Default")
      (node (ref "BT1") (pin "27") (pinfunction "PIO4_27") (pintype "passive+no_connect"))
    )
    (net (code "57") (name "unconnected-(BT1-PIO5-Pad28)") (class "Default")
      (node (ref "BT1") (pin "28") (pinfunction "PIO5_28") (pintype "passive+no_connect"))
    )
    (net (code "58") (name "unconnected-(BT1-PIO6-Pad29)") (class "Default")
      (node (ref "BT1") (pin "29") (pinfunction "PIO6_29") (pintype "passive+no_connect"))
    )
    (net (code "59") (name "unconnected-(BT1-PIO7-Pad30)") (class "Default")
      (node (ref "BT1") (pin "30") (pinfunction "PIO7_30") (pintype "passive+no_connect"))
    )
    (net (code "60") (name "unconnected-(BT1-PIO8-Pad31)") (class "Default")
      (node (ref "BT1") (pin "31") (pinfunction "PIO8_31") (pintype "passive+no_connect"))
    )
    (net (code "61") (name "unconnected-(BT1-PIO9-Pad32)") (class "Default")
      (node (ref "BT1") (pin "32") (pinfunction "PIO9_32") (pintype "passive+no_connect"))
    )
    (net (code "62") (name "unconnected-(BT1-PIO10-Pad33)") (class "Default")
      (node (ref "BT1") (pin "33") (pinfunction "PIO10_33") (pintype "passive+no_connect"))
    )
    (net (code "63") (name "unconnected-(BT1-PIO11-Pad34)") (class "Default")
      (node (ref "BT1") (pin "34") (pinfunction "PIO11_34") (pintype "passive+no_connect"))
    )
    (net (code "64") (name "unconnected-(BT1-RST-Pad11)") (class "Default")
      (node (ref "BT1") (pin "11") (pinfunction "RST_11") (pintype "passive+no_connect"))
    )
    (net (code "65") (name "unconnected-(BT1-RTS-Pad4)") (class "Default")
      (node (ref "BT1") (pin "4") (pinfunction "RTS_4") (pintype "passive+no_connect"))
    )
    (net (code "66") (name "unconnected-(BT1-SPI_CLK-Pad19)") (class "Default")
      (node (ref "BT1") (pin "19") (pinfunction "SPI_CLK_19") (pintype "passive+no_connect"))
    )
    (net (code "67") (name "unconnected-(BT1-SPI_CSB-Pad16)") (class "Default")
      (node (ref "BT1") (pin "16") (pinfunction "SPI_CSB_16") (pintype "passive+no_connect"))
    )
    (net (code "68") (name "unconnected-(BT1-SPI_MISO-Pad18)") (class "Default")
      (node (ref "BT1") (pin "18") (pinfunction "SPI_MISO_18") (pintype "passive+no_connect"))
    )
    (net (code "69") (name "unconnected-(BT1-SPI_MOSI-Pad17)") (class "Default")
      (node (ref "BT1") (pin "17") (pinfunction "SPI_MOSI_17") (pintype "passive+no_connect"))
    )
    (net (code "70") (name "unconnected-(BT1-USB_D+-Pad20)") (class "Default")
      (node (ref "BT1") (pin "20") (pinfunction "USB_D+_20") (pintype "passive+no_connect"))
    )
    (net (code "71") (name "unconnected-(BT1-USB_D--Pad15)") (class "Default")
      (node (ref "BT1") (pin "15") (pinfunction "USB_D-_15") (pintype "passive+no_connect"))
    )
    (net (code "72") (name "unconnected-(LCD1-SD-CS-Pad11)") (class "Default")
      (node (ref "LCD1") (pin "11") (pinfunction "SD-CS_11") (pintype "passive+no_connect"))
    )
    (net (code "73") (name "unconnected-(LCD1-SD-MISO-Pad8)") (class "Default")
      (node (ref "LCD1") (pin "8") (pinfunction "SD-MISO_8") (pintype "passive+no_connect"))
    )
    (net (code "74") (name "unconnected-(LCD1-SD-MOSI-Pad10)") (class "Default")
      (node (ref "LCD1") (pin "10") (pinfunction "SD-MOSI_10") (pintype "passive+no_connect"))
    )
    (net (code "75") (name "unconnected-(LCD1-SD-SCLK-Pad9)") (class "Default")
      (node (ref "LCD1") (pin "9") (pinfunction "SD-SCLK_9") (pintype "passive+no_connect"))
    )
    (net (code "76") (name "unconnected-(R1-CONFIG-Pad5)") (class "Default")
      (node (ref "R1") (pin "5") (pinfunction "CONFIG_5") (pintype "passive+no_connect"))
    )
    (net (code "77") (name "unconnected-(R1-TEST-Pad7)") (class "Default")
      (node (ref "R1") (pin "7") (pinfunction "TEST_7") (pintype "passive+no_connect"))
    )
    (net (code "78") (name "unconnected-(U2-A0-Pad36)") (class "Default")
      (node (ref "U2") (pin "36") (pinfunction "A0_36") (pintype "power_in"))
    )
    (net (code "79") (name "unconnected-(U2-A3-Pad39)") (class "Default")
      (node (ref "U2") (pin "39") (pinfunction "A3_39") (pintype "power_in"))
    )
    (net (code "80") (name "unconnected-(U2-A4-Pad40)") (class "Default")
      (node (ref "U2") (pin "40") (pinfunction "A4_40") (pintype "power_in"))
    )
    (net (code "81") (name "unconnected-(U2-A5-Pad41)") (class "Default")
      (node (ref "U2") (pin "41") (pinfunction "A5_41") (pintype "power_in"))
    )
    (net (code "82") (name "unconnected-(U2-D2{slash}SDA-Pad19)") (class "Default")
      (node (ref "U2") (pin "19") (pinfunction "D2/SDA_19") (pintype "power_in"))
    )
    (net (code "83") (name "unconnected-(U2-D3{slash}PWM{slash}SCL-Pad18)") (class "Default")
      (node (ref "U2") (pin "18") (pinfunction "D3/PWM/SCL_18") (pintype "power_in"))
    )
    (net (code "84") (name "unconnected-(U2-D6{slash}PWM-Pad27)") (class "Default")
      (node (ref "U2") (pin "27") (pinfunction "D6/PWM_27") (pintype "power_in"))
    )
    (net (code "85") (name "unconnected-(U2-D9{slash}PWM-Pad29)") (class "Default")
      (node (ref "U2") (pin "29") (pinfunction "D9/PWM_29") (pintype "power_in"))
    )
    (net (code "86") (name "unconnected-(U2-D10{slash}PWM-Pad30)") (class "Default")
      (node (ref "U2") (pin "30") (pinfunction "D10/PWM_30") (pintype "power_in"))
    )
    (net (code "87") (name "unconnected-(U2-D11{slash}PWM-Pad12)") (class "Default")
      (node (ref "U2") (pin "12") (pinfunction "D11/PWM_12") (pintype "power_in"))
    )
    (net (code "88") (name "unconnected-(U2-D13{slash}PWM-Pad32)") (class "Default")
      (node (ref "U2") (pin "32") (pinfunction "D13/PWM_32") (pintype "power_in"))
    )
    (net (code "89") (name "unconnected-(U4-~{OUT}-Pad4)") (class "Default")
      (node (ref "U4") (pin "4") (pinfunction "~{OUT}_4") (pintype "passive+no_connect"))
    )
    (net (code "90") (name "unconnected-(USB1-ID-Pad4)") (class "Default")
      (node (ref "USB1") (pin "4") (pinfunction "ID_4") (pintype "passive+no_connect"))
    )
  )
)
